# LCD.net
KiCad netlist of a schematic drawn in Altium Designer
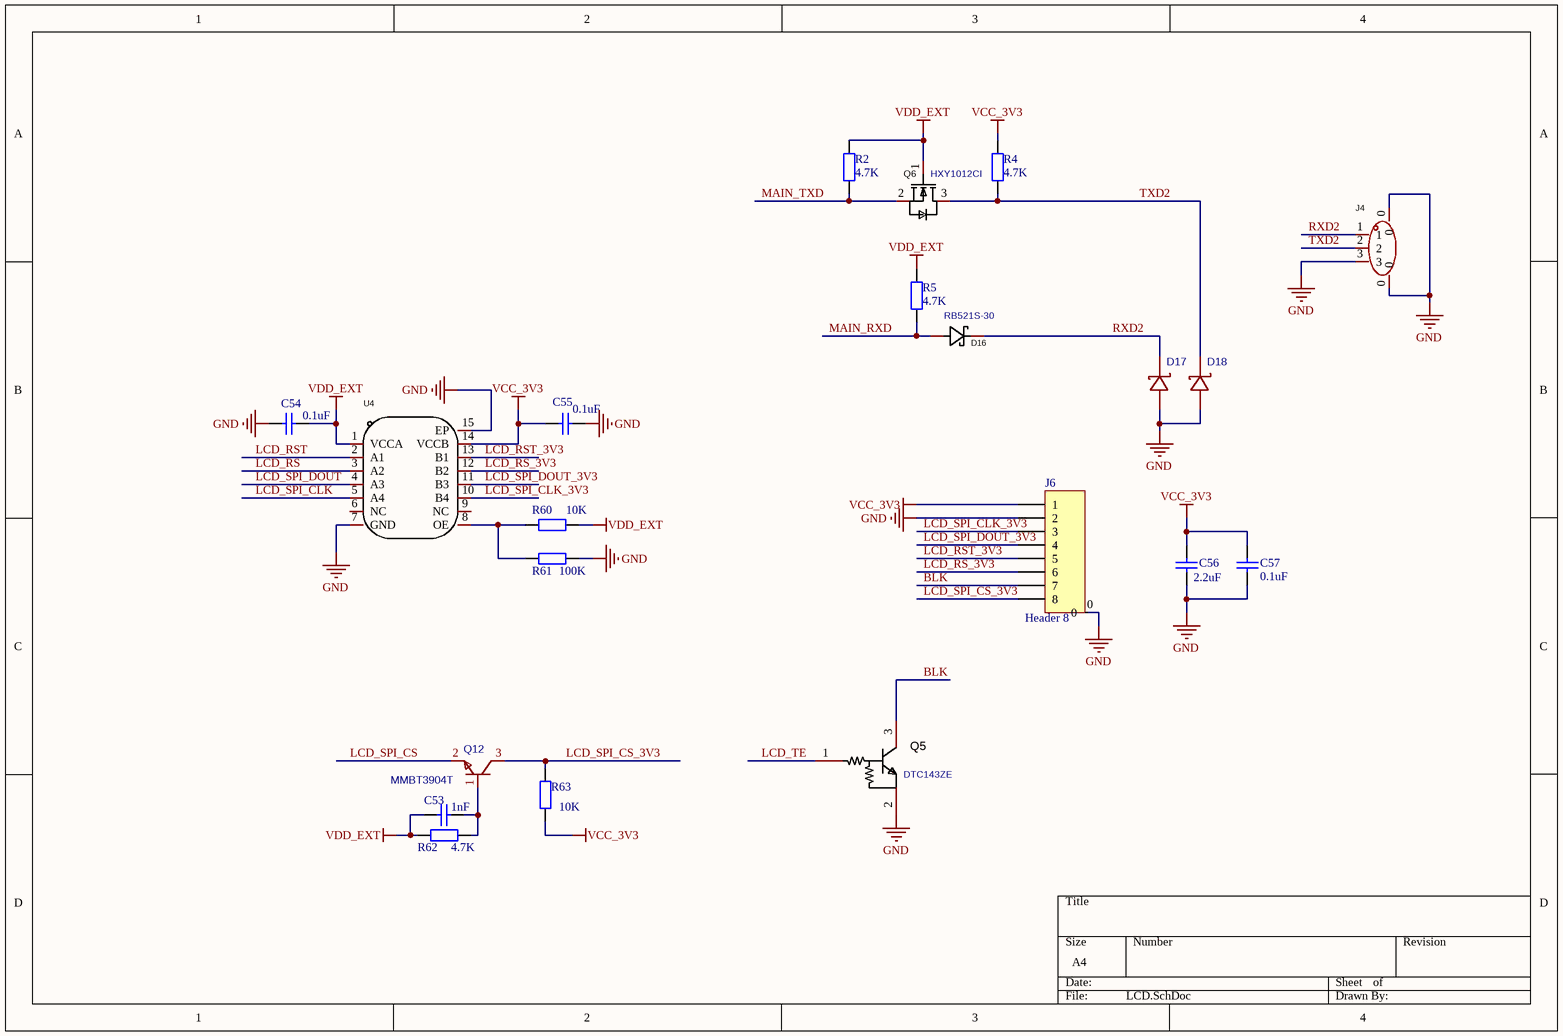
[diagram p0: LCD.SchDoc]

(export (version "E")
  (design (tool "Eeschema 10.0.6"))
  (components
    (comp (ref "C53")
      (value "1nF")
      (footprint "0402C")
      (description "Capacitor")
      (fields (field (name "PUBLISHER") "Altium Limited"))
      (libsource (lib "Miscellaneous Devices") (part "Cap"))
    )
    (comp (ref "C54")
      (value "0.1uF")
      (footprint "0402C")
      (description "Capacitor")
      (fields (field (name "PUBLISHER") "Altium Limited"))
      (libsource (lib "Miscellaneous Devices") (part "Cap"))
    )
    (comp (ref "C55")
      (value "0.1uF")
      (footprint "0402C")
      (description "Capacitor")
      (fields (field (name "PUBLISHER") "Altium Limited"))
      (libsource (lib "Miscellaneous Devices") (part "Cap"))
    )
    (comp (ref "C56")
      (value "2.2uF")
      (footprint "0402C")
      (description "Capacitor")
      (fields (field (name "Comment") "4.7uF") (field (name "PUBLISHER") "Altium Limited"))
      (libsource (lib "Miscellaneous Devices") (part "Cap"))
    )
    (comp (ref "C57")
      (value "0.1uF")
      (footprint "0402C")
      (description "Capacitor")
      (fields (field (name "PUBLISHER") "Altium Limited"))
      (libsource (lib "Miscellaneous Devices") (part "Cap"))
    )
    (comp (ref "D16")
      (value "RB521S-30")
      (footprint "SOD-523_L1.2-W0.8-LS1.6-RD")
      (description "DIODE")
      (fields (field (name "MANUFACTURER") "TWGMC(台湾迪嘉)"))
      (libsource (lib "altium-import") (part "root_2_1N4148WT_C727112_"))
    )
    (comp (ref "D17")
      (value "LESD8LL5.0T5G")
      (footprint "SOD-882_L1.0-W0.6-RD")
      (description "ESD")
      (fields (field (name "BOM_SUPPLIER PART") "C172423") (field (name "CONTRIBUTOR") "LCSC"))
      (libsource (lib "altium-import") (part "root_3_LESD8LL5.0T5G_"))
    )
    (comp (ref "D18")
      (value "LESD8LL5.0T5G")
      (footprint "SOD-882_L1.0-W0.6-RD")
      (description "ESD")
      (fields (field (name "BOM_SUPPLIER PART") "C172423") (field (name "CONTRIBUTOR") "LCSC"))
      (libsource (lib "altium-import") (part "root_3_LESD8LL5.0T5G_"))
    )
    (comp (ref "J4")
      (value "HC-1.25-3PWT")
      (footprint "MX 1.25-WS-3P")
      (description "Connect")
      (fields (field (name "MANUFACTURER") "HCTL(华灿天禄)"))
      (libsource (lib "altium-import") (part "root_0_HC-1.25-3PWT_"))
    )
    (comp (ref "J6")
      (value "Header 8")
      (footprint "MX 1.25-WS-8P")
      (description "Header, 8-Pin")
      (fields (field (name "PUBLISHER") "Altium Limited"))
      (libsource (lib "Miscellaneous Connectors") (part "Header 8"))
    )
    (comp (ref "Q5")
      (value "DTC143ZE")
      (footprint "SOT-523")
      (description "NPN")
      (fields (field (name "MANUFACTURER") "TC(德昌)"))
      (libsource (lib "altium-import") (part "root_0_DTC143ZE_C248787_"))
    )
    (comp (ref "Q6")
      (value "HXY1012CI")
      (footprint "SOT-523")
      (description "NMOS")
      (fields (field (name "MANUFACTURER") "HXY MOSFET(华轩阳电子)"))
      (libsource (lib "altium-import") (part "root_3_HXY1012CI_"))
    )
    (comp (ref "Q12")
      (value "MMBT3904T")
      (footprint "SOT-523")
      (fields (field (name "BOM_SUPPLIER PART") "C61616"))
      (libsource (lib "altium-import") (part "root_1_mirrored_MMBT3904T_"))
    )
    (comp (ref "R2")
      (value "4.7K")
      (footprint "0402R")
      (description "Resistor")
      (fields (field (name "PUBLISHER") "Altium Limited"))
      (libsource (lib "") (part "Res2_1"))
    )
    (comp (ref "R4")
      (value "4.7K")
      (footprint "0402R")
      (description "Resistor")
      (fields (field (name "PUBLISHER") "Altium Limited"))
      (libsource (lib "") (part "Res2_1"))
    )
    (comp (ref "R5")
      (value "4.7K")
      (footprint "0402R")
      (description "Resistor")
      (fields (field (name "PUBLISHER") "Altium Limited"))
      (libsource (lib "") (part "Res2_1"))
    )
    (comp (ref "R60")
      (value "10K")
      (footprint "0402R")
      (description "Resistor")
      (fields (field (name "PUBLISHER") "Altium Limited"))
      (libsource (lib "") (part "Res2_3"))
    )
    (comp (ref "R61")
      (value "100K")
      (footprint "0402R")
      (description "Resistor")
      (fields (field (name "PUBLISHER") "Altium Limited"))
      (libsource (lib "Miscellaneous Devices") (part "Res2"))
    )
    (comp (ref "R62")
      (value "4.7K")
      (footprint "0402R")
      (description "Resistor")
      (fields (field (name "PUBLISHER") "Altium Limited"))
      (libsource (lib "Miscellaneous Devices") (part "Res2"))
    )
    (comp (ref "R63")
      (value "10K")
      (footprint "0402R")
      (description "Resistor")
      (fields (field (name "PUBLISHER") "Altium Limited"))
      (libsource (lib "") (part "Res2_2"))
    )
    (comp (ref "U4")
      (value "TXS0104ERGYR")
      (footprint "VQFN-14_L3.5-W3.5-P0.50-BL-EP")
      (description "电平转换IC")
      (fields (field (name "MANUFACTURER") "TI(德州仪器)"))
      (libsource (lib "altium-import") (part "root_0_TXS0104ERGYR_"))
    )
  )
  (nets
    (net (code "1") (name "/BLK") (class "Default")
      (node (ref "J6") (pin "7") (pinfunction "7_7") (pintype "passive"))
      (node (ref "Q5") (pin "3") (pinfunction "C_3") (pintype "passive"))
    )
    (net (code "2") (name "/LCD_RS") (class "Default")
      (node (ref "U4") (pin "3") (pinfunction "A2_3") (pintype "passive"))
    )
    (net (code "3") (name "/LCD_RST") (class "Default")
      (node (ref "U4") (pin "2") (pinfunction "A1_2") (pintype "passive"))
    )
    (net (code "4") (name "/LCD_RST_3V3") (class "Default")
      (node (ref "J6") (pin "5") (pinfunction "5_5") (pintype "passive"))
      (node (ref "U4") (pin "13") (pinfunction "B1_13") (pintype "passive"))
    )
    (net (code "5") (name "/LCD_RS_3V3") (class "Default")
      (node (ref "J6") (pin "6") (pinfunction "6_6") (pintype "passive"))
      (node (ref "U4") (pin "12") (pinfunction "B2_12") (pintype "passive"))
    )
    (net (code "6") (name "/LCD_SPI_CLK") (class "Default")
      (node (ref "U4") (pin "5") (pinfunction "A4_5") (pintype "passive"))
    )
    (net (code "7") (name "/LCD_SPI_CLK_3V3") (class "Default")
      (node (ref "J6") (pin "3") (pinfunction "3_3") (pintype "passive"))
      (node (ref "U4") (pin "10") (pinfunction "B4_10") (pintype "passive"))
    )
    (net (code "8") (name "/LCD_SPI_CS") (class "Default")
      (node (ref "Q12") (pin "2") (pinfunction "E_2") (pintype "passive"))
    )
    (net (code "9") (name "/LCD_SPI_CS_3V3") (class "Default")
      (node (ref "J6") (pin "8") (pinfunction "8_8") (pintype "passive"))
      (node (ref "Q12") (pin "3") (pinfunction "C_3") (pintype "passive"))
      (node (ref "R63") (pin "2") (pinfunction "2_2") (pintype "passive"))
    )
    (net (code "10") (name "/LCD_SPI_DOUT") (class "Default")
      (node (ref "U4") (pin "4") (pinfunction "A3_4") (pintype "passive"))
    )
    (net (code "11") (name "/LCD_SPI_DOUT_3V3") (class "Default")
      (node (ref "J6") (pin "4") (pinfunction "4_4") (pintype "passive"))
      (node (ref "U4") (pin "11") (pinfunction "B3_11") (pintype "passive"))
    )
    (net (code "12") (name "/LCD_TE") (class "Default")
      (node (ref "Q5") (pin "1") (pinfunction "B_1") (pintype "passive"))
    )
    (net (code "13") (name "/MAIN_RXD") (class "Default")
      (node (ref "D16") (pin "2") (pinfunction "A_2") (pintype "passive"))
      (node (ref "R5") (pin "2") (pinfunction "2_2") (pintype "passive"))
    )
    (net (code "14") (name "/MAIN_TXD") (class "Default")
      (node (ref "Q6") (pin "2") (pinfunction "S_2") (pintype "passive"))
      (node (ref "R2") (pin "2") (pinfunction "2_2") (pintype "passive"))
    )
    (net (code "15") (name "/RXD2") (class "Default")
      (node (ref "D16") (pin "1") (pinfunction "C_1") (pintype "passive"))
      (node (ref "D17") (pin "1") (pinfunction "C_1") (pintype "passive"))
      (node (ref "J4") (pin "1") (pinfunction "1_1") (pintype "passive"))
    )
    (net (code "16") (name "/TXD2") (class "Default")
      (node (ref "D18") (pin "1") (pinfunction "C_1") (pintype "passive"))
      (node (ref "J4") (pin "2") (pinfunction "2_2") (pintype "passive"))
      (node (ref "Q6") (pin "3") (pinfunction "D_3") (pintype "passive"))
      (node (ref "R4") (pin "2") (pinfunction "2_2") (pintype "passive"))
    )
    (net (code "17") (name "GND") (class "Default")
      (node (ref "C54") (pin "1") (pinfunction "1_1") (pintype "passive"))
      (node (ref "C55") (pin "2") (pinfunction "2_2") (pintype "passive"))
      (node (ref "C56") (pin "1") (pinfunction "1_1") (pintype "passive"))
      (node (ref "C57") (pin "1") (pinfunction "1_1") (pintype "passive"))
      (node (ref "D17") (pin "2") (pinfunction "A_2") (pintype "passive"))
      (node (ref "D18") (pin "2") (pinfunction "A_2") (pintype "passive"))
      (node (ref "J4") (pin "0") (pinfunction "0_0") (pintype "passive"))
      (node (ref "J4") (pin "3") (pinfunction "3_3") (pintype "passive"))
      (node (ref "J6") (pin "0") (pinfunction "0_0") (pintype "passive"))
      (node (ref "J6") (pin "2") (pinfunction "2_2") (pintype "passive"))
      (node (ref "Q5") (pin "2") (pinfunction "E_2") (pintype "passive"))
      (node (ref "R61") (pin "2") (pinfunction "2_2") (pintype "passive"))
      (node (ref "U4") (pin "15") (pinfunction "EP_15") (pintype "passive"))
      (node (ref "U4") (pin "7") (pinfunction "GND_7") (pintype "passive"))
    )
    (net (code "18") (name "Net-(Q12-B)") (class "Default")
      (node (ref "C53") (pin "2") (pinfunction "2_2") (pintype "passive"))
      (node (ref "Q12") (pin "1") (pinfunction "B_1") (pintype "passive"))
      (node (ref "R62") (pin "2") (pinfunction "2_2") (pintype "passive"))
    )
    (net (code "19") (name "Net-(U4-OE)") (class "Default")
      (node (ref "R60") (pin "2") (pinfunction "2_2") (pintype "passive"))
      (node (ref "R61") (pin "1") (pinfunction "1_1") (pintype "passive"))
      (node (ref "U4") (pin "8") (pinfunction "OE_8") (pintype "passive"))
    )
    (net (code "20") (name "VCC_3V3") (class "Default")
      (node (ref "C55") (pin "1") (pinfunction "1_1") (pintype "passive"))
      (node (ref "C56") (pin "2") (pinfunction "2_2") (pintype "passive"))
      (node (ref "C57") (pin "2") (pinfunction "2_2") (pintype "passive"))
      (node (ref "J6") (pin "1") (pinfunction "1_1") (pintype "passive"))
      (node (ref "R4") (pin "1") (pinfunction "1_1") (pintype "passive"))
      (node (ref "R63") (pin "1") (pinfunction "1_1") (pintype "passive"))
      (node (ref "U4") (pin "14") (pinfunction "VCCB_14") (pintype "passive"))
    )
    (net (code "21") (name "VDD_EXT") (class "Default")
      (node (ref "C53") (pin "1") (pinfunction "1_1") (pintype "passive"))
      (node (ref "C54") (pin "2") (pinfunction "2_2") (pintype "passive"))
      (node (ref "Q6") (pin "1") (pinfunction "G_1") (pintype "passive"))
      (node (ref "R2") (pin "1") (pinfunction "1_1") (pintype "passive"))
      (node (ref "R5") (pin "1") (pinfunction "1_1") (pintype "passive"))
      (node (ref "R60") (pin "1") (pinfunction "1_1") (pintype "passive"))
      (node (ref "R62") (pin "1") (pinfunction "1_1") (pintype "passive"))
      (node (ref "U4") (pin "1") (pinfunction "VCCA_1") (pintype "passive"))
    )
    (net (code "22") (name "unconnected-(U4-NC-Pad6)") (class "Default")
      (node (ref "U4") (pin "6") (pinfunction "NC_6") (pintype "passive"))
    )
    (net (code "23") (name "unconnected-(U4-NC-Pad9)") (class "Default")
      (node (ref "U4") (pin "9") (pinfunction "NC_9") (pintype "passive"))
    )
  )
)
